# USB_Type_C_PD_Schematic.net
KiCad netlist of a schematic drawn in EAGLE
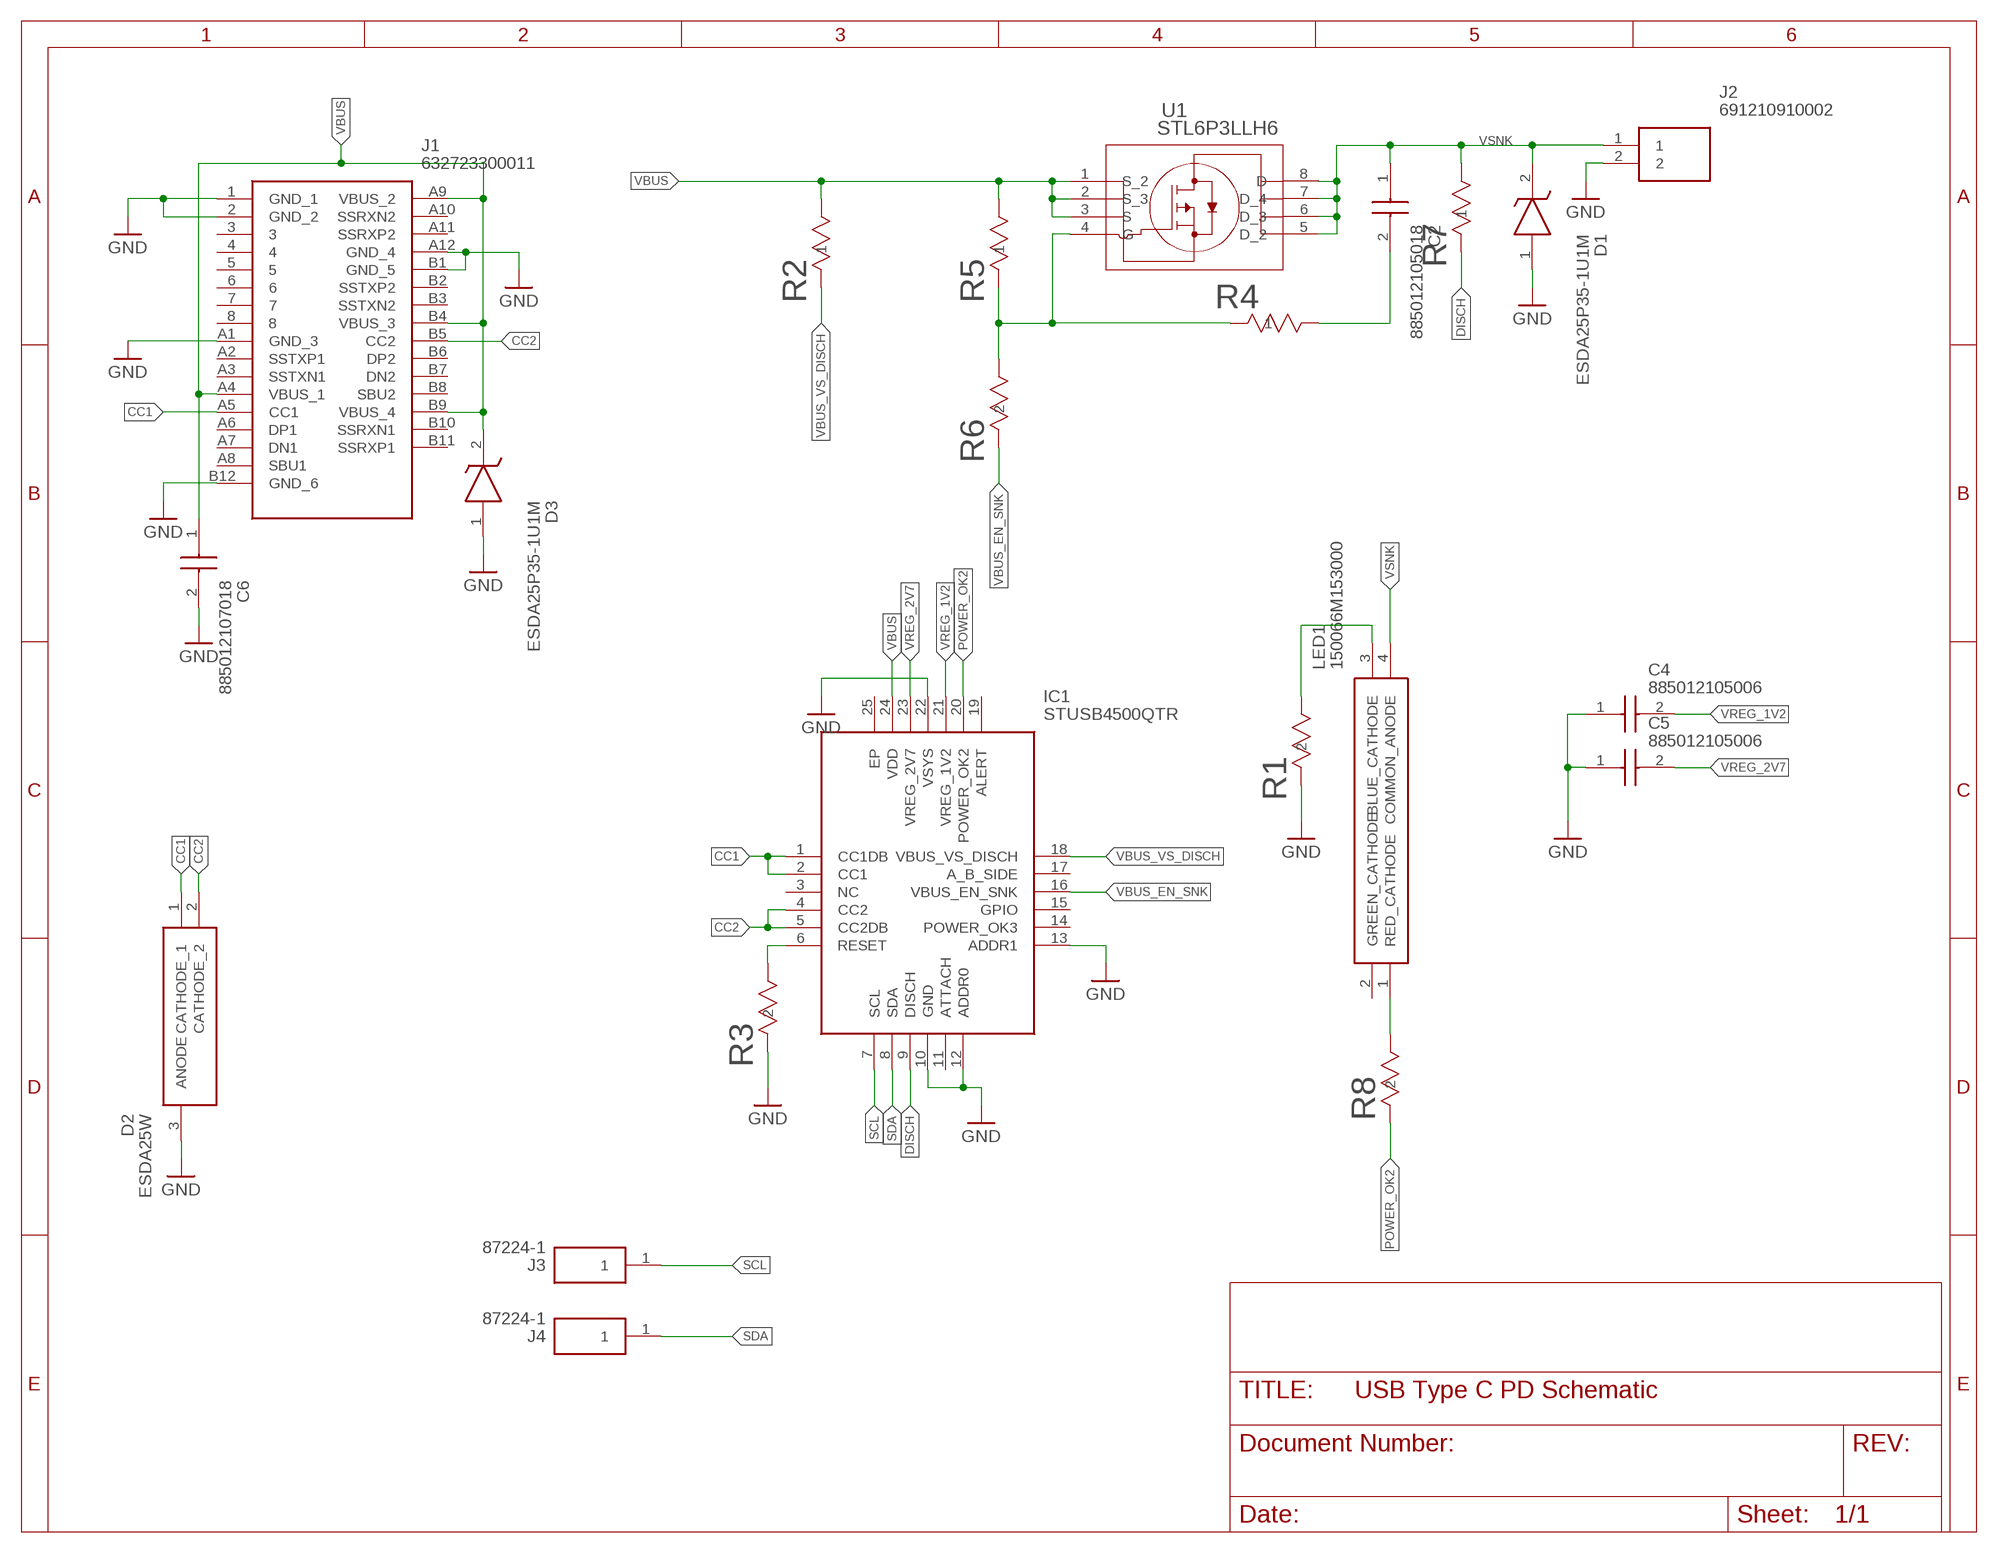
[diagram p0: schematic, sheet 1]

(export (version "E")
  (design (tool "Eeschema 10.0.6"))
  (components
    (comp (ref "C2")
      (value "885012105018")
      (footprint "eagle-import:CAPC1005X55N")
      (fields (field (name "MOUSER_PART_NUMBER") "710-885012105018"))
      (libsource (lib "eagle-import") (part "885012105018"))
    )
    (comp (ref "C4")
      (value "885012105006")
      (footprint "eagle-import:CAPC1005X55N")
      (libsource (lib "eagle-import") (part "885012105006"))
    )
    (comp (ref "C5")
      (value "885012105006")
      (footprint "eagle-import:CAPC1005X55N")
      (libsource (lib "eagle-import") (part "885012105006"))
    )
    (comp (ref "C6")
      (value "885012107018")
      (footprint "eagle-import:CAPC2012X145N")
      (fields (field (name "MOUSER_PART_NUMBER") "710-885012107018"))
      (libsource (lib "eagle-import") (part "885012107018"))
    )
    (comp (ref "D1")
      (value "ESDA25P35-1U1M")
      (footprint "eagle-import:ESDA8P801U1M")
      (fields (field (name "MOUSER_PART_NUMBER") "511-ESDA25P35-1U1M"))
      (libsource (lib "eagle-import") (part "ESDA25P35-1U1M"))
    )
    (comp (ref "D2")
      (value "ESDA25W")
      (footprint "eagle-import:SOT65P210X110-3N")
      (fields (field (name "MOUSER_PART_NUMBER") "511-ESDA25W"))
      (libsource (lib "eagle-import") (part "ESDA25W"))
    )
    (comp (ref "D3")
      (value "ESDA25P35-1U1M")
      (footprint "eagle-import:ESDA8P801U1M")
      (fields (field (name "MOUSER_PART_NUMBER") "511-ESDA25P35-1U1M"))
      (libsource (lib "eagle-import") (part "ESDA25P35-1U1M"))
    )
    (comp (ref "IC1")
      (value "STUSB4500QTR")
      (footprint "eagle-import:QFN50P400X400X100-25N")
      (fields (field (name "MOUSER_PART_NUMBER") "511-STUSB4500QTR"))
      (libsource (lib "eagle-import") (part "STUSB4500QTR"))
    )
    (comp (ref "J1")
      (value "632723300011")
      (footprint "eagle-import:632723300011")
      (fields (field (name "MOUSER_PART_NUMBER") "710-632723300011"))
      (libsource (lib "eagle-import") (part "632723300011"))
    )
    (comp (ref "J2")
      (value "691210910002")
      (footprint "eagle-import:691210910002")
      (fields (field (name "MOUSER_PART_NUMBER") "710-691210910002"))
      (libsource (lib "eagle-import") (part "691210910002"))
    )
    (comp (ref "J3")
      (value "87224-1")
      (footprint "eagle-import:HDRV1W66P0X254_1X1_213X254X107")
      (fields (field (name "MOUSER_PART_NUMBER") "571-872241"))
      (libsource (lib "eagle-import") (part "87224-1"))
    )
    (comp (ref "J4")
      (value "87224-1")
      (footprint "eagle-import:HDRV1W66P0X254_1X1_213X254X107")
      (fields (field (name "MOUSER_PART_NUMBER") "571-872241"))
      (libsource (lib "eagle-import") (part "87224-1"))
    )
    (comp (ref "LED1")
      (value "150066M153000")
      (footprint "eagle-import:150066M153000")
      (fields (field (name "MOUSER_PART_NUMBER") "710-150066M153000"))
      (libsource (lib "eagle-import") (part "150066M153000"))
    )
    (comp (ref "R1")
      (value "RC0402JR-0722KL")
      (footprint "eagle-import:RC0402N_YAG")
      (fields (field (name "COPYRIGHT") "Copyright (C) 2023 Ultra Librarian. All rights reserved."))
      (libsource (lib "eagle-import") (part "RC0402JR-0722KL"))
    )
    (comp (ref "R2")
      (value "RNCP0603FTD1K00")
      (footprint "eagle-import:STA_RNCP0603_STP")
      (fields (field (name "COPYRIGHT") "Copyright (C) 2023 Ultra Librarian. All rights reserved."))
      (libsource (lib "eagle-import") (part "RNCP0603FTD1K00"))
    )
    (comp (ref "R3")
      (value "RC0402JR-0710KL")
      (footprint "eagle-import:RC0402N_YAG")
      (fields (field (name "COPYRIGHT") "Copyright (C) 2023 Ultra Librarian. All rights reserved."))
      (libsource (lib "eagle-import") (part "RC0402JR-0710KL"))
    )
    (comp (ref "R4")
      (value "RC0201FR-07100RL")
      (footprint "eagle-import:YAG_R0201_YAG")
      (fields (field (name "COPYRIGHT") "Copyright (C) 2023 Ultra Librarian. All rights reserved."))
      (libsource (lib "eagle-import") (part "RC0201FR-07100RL"))
    )
    (comp (ref "R5")
      (value "RC0603FR-07100KL")
      (footprint "eagle-import:RC0603N_YAG")
      (fields (field (name "COPYRIGHT") "Copyright (C) 2023 Ultra Librarian. All rights reserved."))
      (libsource (lib "eagle-import") (part "RC0603FR-07100KL"))
    )
    (comp (ref "R6")
      (value "RC0402JR-0722KL")
      (footprint "eagle-import:RC0402N_YAG")
      (fields (field (name "COPYRIGHT") "Copyright (C) 2023 Ultra Librarian. All rights reserved."))
      (libsource (lib "eagle-import") (part "RC0402JR-0722KL"))
    )
    (comp (ref "R7")
      (value "RNCP0603FTD1K00")
      (footprint "eagle-import:STA_RNCP0603_STP")
      (fields (field (name "COPYRIGHT") "Copyright (C) 2023 Ultra Librarian. All rights reserved."))
      (libsource (lib "eagle-import") (part "RNCP0603FTD1K00"))
    )
    (comp (ref "R8")
      (value "RC0402JR-0722KL")
      (footprint "eagle-import:RC0402N_YAG")
      (fields (field (name "COPYRIGHT") "Copyright (C) 2023 Ultra Librarian. All rights reserved."))
      (libsource (lib "eagle-import") (part "RC0402JR-0722KL"))
    )
    (comp (ref "U1")
      (value "STL6P3LLH6")
      (footprint "eagle-import:POWERFLAT_3P3X3P3_STM")
      (fields (field (name "COPYRIGHT") "Copyright (C) 2023 Ultra Librarian. All rights reserved."))
      (libsource (lib "eagle-import") (part "STL6P3LLH6"))
    )
  )
  (nets
    (net (code "1") (name "CC1") (class "Default")
      (node (ref "D2") (pin "1") (pinfunction "CATHODE_1_1") (pintype "bidirectional"))
      (node (ref "IC1") (pin "1") (pinfunction "CC1DB_1") (pintype "bidirectional"))
      (node (ref "IC1") (pin "2") (pinfunction "CC1_2") (pintype "bidirectional"))
      (node (ref "J1") (pin "A5") (pinfunction "CC1_A5") (pintype "bidirectional"))
    )
    (net (code "2") (name "CC2") (class "Default")
      (node (ref "D2") (pin "2") (pinfunction "CATHODE_2_2") (pintype "bidirectional"))
      (node (ref "IC1") (pin "4") (pinfunction "CC2_4") (pintype "bidirectional"))
      (node (ref "IC1") (pin "5") (pinfunction "CC2DB_5") (pintype "bidirectional"))
      (node (ref "J1") (pin "B5") (pinfunction "CC2_B5") (pintype "bidirectional"))
    )
    (net (code "3") (name "DISCH") (class "Default")
      (node (ref "IC1") (pin "9") (pinfunction "DISCH_9") (pintype "bidirectional"))
      (node (ref "R7") (pin "1") (pinfunction "1_1") (pintype "passive"))
    )
    (net (code "4") (name "GND") (class "Default")
      (node (ref "C4") (pin "1") (pinfunction "1_1") (pintype "bidirectional"))
      (node (ref "C5") (pin "1") (pinfunction "1_1") (pintype "bidirectional"))
      (node (ref "C6") (pin "2") (pinfunction "2_2") (pintype "bidirectional"))
      (node (ref "D1") (pin "1") (pinfunction "A_1") (pintype "bidirectional"))
      (node (ref "D2") (pin "3") (pinfunction "ANODE_3") (pintype "bidirectional"))
      (node (ref "D3") (pin "1") (pinfunction "A_1") (pintype "bidirectional"))
      (node (ref "IC1") (pin "10") (pinfunction "GND_10") (pintype "bidirectional"))
      (node (ref "IC1") (pin "12") (pinfunction "ADDR0_12") (pintype "bidirectional"))
      (node (ref "IC1") (pin "13") (pinfunction "ADDR1_13") (pintype "bidirectional"))
      (node (ref "IC1") (pin "22") (pinfunction "VSYS_22") (pintype "bidirectional"))
      (node (ref "J1") (pin "1") (pinfunction "GND_1_1") (pintype "bidirectional"))
      (node (ref "J1") (pin "2") (pinfunction "GND_2_2") (pintype "bidirectional"))
      (node (ref "J1") (pin "A1") (pinfunction "GND_3_A1") (pintype "bidirectional"))
      (node (ref "J1") (pin "A12") (pinfunction "GND_4_A12") (pintype "bidirectional"))
      (node (ref "J1") (pin "B1") (pinfunction "GND_5_B1") (pintype "bidirectional"))
      (node (ref "J1") (pin "B12") (pinfunction "GND_6_B12") (pintype "bidirectional"))
      (node (ref "J2") (pin "2") (pinfunction "2_2") (pintype "bidirectional"))
      (node (ref "R1") (pin "2") (pinfunction "2_2") (pintype "passive"))
      (node (ref "R3") (pin "2") (pinfunction "2_2") (pintype "passive"))
    )
    (net (code "5") (name "Net-(C2-Pad2)") (class "Default")
      (node (ref "C2") (pin "2") (pinfunction "2_2") (pintype "bidirectional"))
      (node (ref "R4") (pin "2") (pinfunction "2_2") (pintype "passive"))
    )
    (net (code "6") (name "Net-(IC1-RESET)") (class "Default")
      (node (ref "IC1") (pin "6") (pinfunction "RESET_6") (pintype "bidirectional"))
      (node (ref "R3") (pin "1") (pinfunction "1_1") (pintype "passive"))
    )
    (net (code "7") (name "Net-(LED1-BLUE_CATHODE)") (class "Default")
      (node (ref "LED1") (pin "3") (pinfunction "BLUE_CATHODE_3") (pintype "bidirectional"))
      (node (ref "R1") (pin "1") (pinfunction "1_1") (pintype "passive"))
    )
    (net (code "8") (name "Net-(LED1-RED_CATHODE)") (class "Default")
      (node (ref "LED1") (pin "1") (pinfunction "RED_CATHODE_1") (pintype "bidirectional"))
      (node (ref "R8") (pin "1") (pinfunction "1_1") (pintype "passive"))
    )
    (net (code "9") (name "Net-(U1-G)") (class "Default")
      (node (ref "R4") (pin "1") (pinfunction "1_1") (pintype "passive"))
      (node (ref "R5") (pin "1") (pinfunction "1_1") (pintype "passive"))
      (node (ref "R6") (pin "1") (pinfunction "1_1") (pintype "passive"))
      (node (ref "U1") (pin "4") (pinfunction "G_4") (pintype "passive"))
    )
    (net (code "10") (name "POWER_OK2") (class "Default")
      (node (ref "IC1") (pin "20") (pinfunction "POWER_OK2_20") (pintype "bidirectional"))
      (node (ref "R8") (pin "2") (pinfunction "2_2") (pintype "passive"))
    )
    (net (code "11") (name "SCL") (class "Default")
      (node (ref "IC1") (pin "7") (pinfunction "SCL_7") (pintype "bidirectional"))
      (node (ref "J3") (pin "1") (pinfunction "1_1") (pintype "bidirectional"))
    )
    (net (code "12") (name "SDA") (class "Default")
      (node (ref "IC1") (pin "8") (pinfunction "SDA_8") (pintype "bidirectional"))
      (node (ref "J4") (pin "1") (pinfunction "1_1") (pintype "bidirectional"))
    )
    (net (code "13") (name "VBUS") (class "Default")
      (node (ref "C6") (pin "1") (pinfunction "1_1") (pintype "bidirectional"))
      (node (ref "D3") (pin "2") (pinfunction "K_2") (pintype "bidirectional"))
      (node (ref "IC1") (pin "24") (pinfunction "VDD_24") (pintype "bidirectional"))
      (node (ref "J1") (pin "A4") (pinfunction "VBUS_1_A4") (pintype "bidirectional"))
      (node (ref "J1") (pin "A9") (pinfunction "VBUS_2_A9") (pintype "bidirectional"))
      (node (ref "J1") (pin "B4") (pinfunction "VBUS_3_B4") (pintype "bidirectional"))
      (node (ref "J1") (pin "B9") (pinfunction "VBUS_4_B9") (pintype "bidirectional"))
      (node (ref "R2") (pin "2") (pinfunction "2_2") (pintype "passive"))
      (node (ref "R5") (pin "2") (pinfunction "2_2") (pintype "passive"))
      (node (ref "U1") (pin "1") (pinfunction "S_2_1") (pintype "passive"))
      (node (ref "U1") (pin "2") (pinfunction "S_3_2") (pintype "passive"))
      (node (ref "U1") (pin "3") (pinfunction "S_3") (pintype "passive"))
    )
    (net (code "14") (name "VBUS_EN_SNK") (class "Default")
      (node (ref "IC1") (pin "16") (pinfunction "VBUS_EN_SNK_16") (pintype "bidirectional"))
      (node (ref "R6") (pin "2") (pinfunction "2_2") (pintype "passive"))
    )
    (net (code "15") (name "VBUS_VS_DISCH") (class "Default")
      (node (ref "IC1") (pin "18") (pinfunction "VBUS_VS_DISCH_18") (pintype "bidirectional"))
      (node (ref "R2") (pin "1") (pinfunction "1_1") (pintype "passive"))
    )
    (net (code "16") (name "VREG_1V2") (class "Default")
      (node (ref "C4") (pin "2") (pinfunction "2_2") (pintype "bidirectional"))
      (node (ref "IC1") (pin "21") (pinfunction "VREG_1V2_21") (pintype "bidirectional"))
    )
    (net (code "17") (name "VREG_2V7") (class "Default")
      (node (ref "C5") (pin "2") (pinfunction "2_2") (pintype "bidirectional"))
      (node (ref "IC1") (pin "23") (pinfunction "VREG_2V7_23") (pintype "bidirectional"))
    )
    (net (code "18") (name "VSNK") (class "Default")
      (node (ref "C2") (pin "1") (pinfunction "1_1") (pintype "bidirectional"))
      (node (ref "D1") (pin "2") (pinfunction "K_2") (pintype "bidirectional"))
      (node (ref "J2") (pin "1") (pinfunction "1_1") (pintype "bidirectional"))
      (node (ref "LED1") (pin "4") (pinfunction "COMMON_ANODE_4") (pintype "bidirectional"))
      (node (ref "R7") (pin "2") (pinfunction "2_2") (pintype "passive"))
      (node (ref "U1") (pin "5") (pinfunction "D_2_5") (pintype "passive"))
      (node (ref "U1") (pin "6") (pinfunction "D_3_6") (pintype "passive"))
      (node (ref "U1") (pin "7") (pinfunction "D_4_7") (pintype "passive"))
      (node (ref "U1") (pin "8") (pinfunction "D_8") (pintype "passive"))
    )
    (net (code "19") (name "unconnected-(IC1-ALERT-Pad19)") (class "Default")
      (node (ref "IC1") (pin "19") (pinfunction "ALERT_19") (pintype "bidirectional"))
    )
    (net (code "20") (name "unconnected-(IC1-ATTACH-Pad11)") (class "Default")
      (node (ref "IC1") (pin "11") (pinfunction "ATTACH_11") (pintype "bidirectional"))
    )
    (net (code "21") (name "unconnected-(IC1-A_B_SIDE-Pad17)") (class "Default")
      (node (ref "IC1") (pin "17") (pinfunction "A_B_SIDE_17") (pintype "bidirectional"))
    )
    (net (code "22") (name "unconnected-(IC1-EP-Pad25)") (class "Default")
      (node (ref "IC1") (pin "25") (pinfunction "EP_25") (pintype "bidirectional"))
    )
    (net (code "23") (name "unconnected-(IC1-GPIO-Pad15)") (class "Default")
      (node (ref "IC1") (pin "15") (pinfunction "GPIO_15") (pintype "bidirectional"))
    )
    (net (code "24") (name "unconnected-(IC1-NC-Pad3)") (class "Default")
      (node (ref "IC1") (pin "3") (pinfunction "NC_3") (pintype "no_connect"))
    )
    (net (code "25") (name "unconnected-(IC1-POWER_OK3-Pad14)") (class "Default")
      (node (ref "IC1") (pin "14") (pinfunction "POWER_OK3_14") (pintype "bidirectional"))
    )
    (net (code "26") (name "unconnected-(J1-DN1-PadA7)") (class "Default")
      (node (ref "J1") (pin "A7") (pinfunction "DN1_A7") (pintype "bidirectional"))
    )
    (net (code "27") (name "unconnected-(J1-DN2-PadB7)") (class "Default")
      (node (ref "J1") (pin "B7") (pinfunction "DN2_B7") (pintype "bidirectional"))
    )
    (net (code "28") (name "unconnected-(J1-DP1-PadA6)") (class "Default")
      (node (ref "J1") (pin "A6") (pinfunction "DP1_A6") (pintype "bidirectional"))
    )
    (net (code "29") (name "unconnected-(J1-DP2-PadB6)") (class "Default")
      (node (ref "J1") (pin "B6") (pinfunction "DP2_B6") (pintype "bidirectional"))
    )
    (net (code "30") (name "unconnected-(J1-Pad3)") (class "Default")
      (node (ref "J1") (pin "3") (pinfunction "3_3") (pintype "bidirectional"))
    )
    (net (code "31") (name "unconnected-(J1-Pad4)") (class "Default")
      (node (ref "J1") (pin "4") (pinfunction "4_4") (pintype "bidirectional"))
    )
    (net (code "32") (name "unconnected-(J1-Pad5)") (class "Default")
      (node (ref "J1") (pin "5") (pinfunction "5_5") (pintype "bidirectional"))
    )
    (net (code "33") (name "unconnected-(J1-Pad6)") (class "Default")
      (node (ref "J1") (pin "6") (pinfunction "6_6") (pintype "bidirectional"))
    )
    (net (code "34") (name "unconnected-(J1-Pad7)") (class "Default")
      (node (ref "J1") (pin "7") (pinfunction "7_7") (pintype "bidirectional"))
    )
    (net (code "35") (name "unconnected-(J1-Pad8)") (class "Default")
      (node (ref "J1") (pin "8") (pinfunction "8_8") (pintype "bidirectional"))
    )
    (net (code "36") (name "unconnected-(J1-SBU1-PadA8)") (class "Default")
      (node (ref "J1") (pin "A8") (pinfunction "SBU1_A8") (pintype "bidirectional"))
    )
    (net (code "37") (name "unconnected-(J1-SBU2-PadB8)") (class "Default")
      (node (ref "J1") (pin "B8") (pinfunction "SBU2_B8") (pintype "bidirectional"))
    )
    (net (code "38") (name "unconnected-(J1-SSRXN1-PadB10)") (class "Default")
      (node (ref "J1") (pin "B10") (pinfunction "SSRXN1_B10") (pintype "bidirectional"))
    )
    (net (code "39") (name "unconnected-(J1-SSRXN2-PadA10)") (class "Default")
      (node (ref "J1") (pin "A10") (pinfunction "SSRXN2_A10") (pintype "bidirectional"))
    )
    (net (code "40") (name "unconnected-(J1-SSRXP1-PadB11)") (class "Default")
      (node (ref "J1") (pin "B11") (pinfunction "SSRXP1_B11") (pintype "bidirectional"))
    )
    (net (code "41") (name "unconnected-(J1-SSRXP2-PadA11)") (class "Default")
      (node (ref "J1") (pin "A11") (pinfunction "SSRXP2_A11") (pintype "bidirectional"))
    )
    (net (code "42") (name "unconnected-(J1-SSTXN1-PadA3)") (class "Default")
      (node (ref "J1") (pin "A3") (pinfunction "SSTXN1_A3") (pintype "bidirectional"))
    )
    (net (code "43") (name "unconnected-(J1-SSTXN2-PadB3)") (class "Default")
      (node (ref "J1") (pin "B3") (pinfunction "SSTXN2_B3") (pintype "bidirectional"))
    )
    (net (code "44") (name "unconnected-(J1-SSTXP1-PadA2)") (class "Default")
      (node (ref "J1") (pin "A2") (pinfunction "SSTXP1_A2") (pintype "bidirectional"))
    )
    (net (code "45") (name "unconnected-(J1-SSTXP2-PadB2)") (class "Default")
      (node (ref "J1") (pin "B2") (pinfunction "SSTXP2_B2") (pintype "bidirectional"))
    )
    (net (code "46") (name "unconnected-(LED1-GREEN_CATHODE-Pad2)") (class "Default")
      (node (ref "LED1") (pin "2") (pinfunction "GREEN_CATHODE_2") (pintype "bidirectional"))
    )
  )
)
